# dGPS_mainBoard.net
KiCad netlist of a schematic drawn in EAGLE
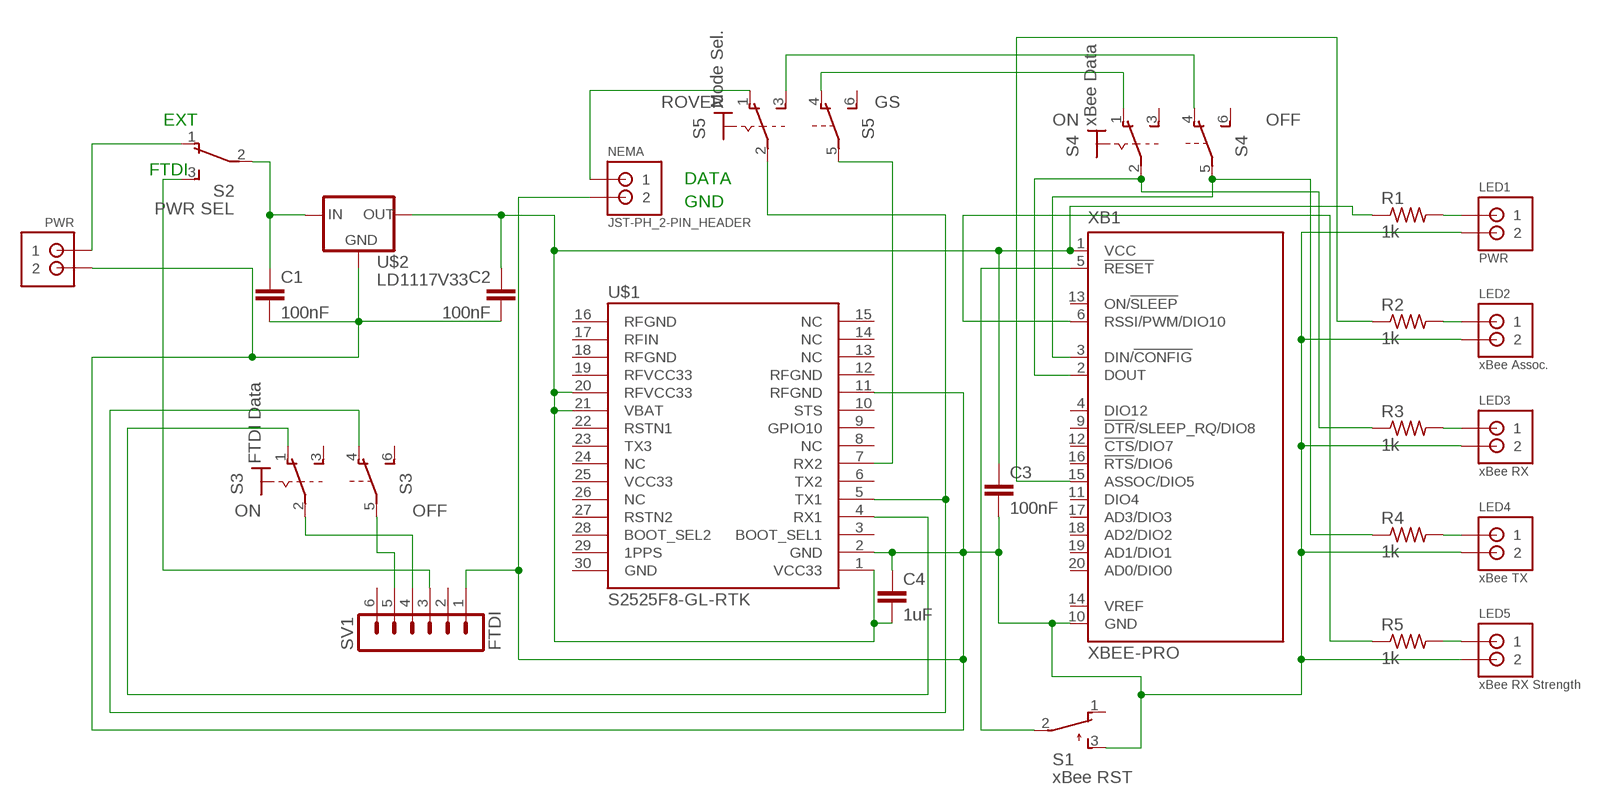
[diagram p0: schematic, sheet 1]

(export (version "E")
  (design (tool "Eeschema 10.0.6"))
  (components
    (comp (ref "C1")
      (value "100nF")
      (footprint "eagle-import:C2.5-5")
      (libsource (lib "eagle-import") (part "C2.5/5"))
    )
    (comp (ref "C2")
      (value "100nF")
      (footprint "eagle-import:C2.5-5")
      (libsource (lib "eagle-import") (part "C2.5/5"))
    )
    (comp (ref "C3")
      (value "100nF")
      (footprint "eagle-import:C2.5-5")
      (libsource (lib "eagle-import") (part "C2.5/5"))
    )
    (comp (ref "C4")
      (value "1uF")
      (footprint "eagle-import:C2.5-5")
      (libsource (lib "eagle-import") (part "C2.5/5"))
    )
    (comp (ref "LED1")
      (value "PWR")
      (footprint "eagle-import:JST_B2B-PH_HEADER")
      (libsource (lib "eagle-import") (part "JST-PH_2-PIN_HEADER"))
    )
    (comp (ref "LED2")
      (value "xBee Assoc.")
      (footprint "eagle-import:JST_B2B-PH_HEADER")
      (libsource (lib "eagle-import") (part "JST-PH_2-PIN_HEADER"))
    )
    (comp (ref "LED3")
      (value "xBee RX")
      (footprint "eagle-import:JST_B2B-PH_HEADER")
      (libsource (lib "eagle-import") (part "JST-PH_2-PIN_HEADER"))
    )
    (comp (ref "LED4")
      (value "xBee TX")
      (footprint "eagle-import:JST_B2B-PH_HEADER")
      (libsource (lib "eagle-import") (part "JST-PH_2-PIN_HEADER"))
    )
    (comp (ref "LED5")
      (value "xBee RX Strength")
      (footprint "eagle-import:JST_B2B-PH_HEADER")
      (libsource (lib "eagle-import") (part "JST-PH_2-PIN_HEADER"))
    )
    (comp (ref "NEMA")
      (value "JST-PH_2-PIN_HEADER")
      (footprint "eagle-import:JST_B2B-PH_HEADER")
      (libsource (lib "eagle-import") (part "JST-PH_2-PIN_HEADER"))
    )
    (comp (ref "PWR")
      (value "JST-PH_2-PIN_HEADER")
      (footprint "eagle-import:JST_B2B-PH_HEADER")
      (libsource (lib "eagle-import") (part "JST-PH_2-PIN_HEADER"))
    )
    (comp (ref "R1")
      (value "1k")
      (footprint "eagle-import:0204_5")
      (libsource (lib "eagle-import") (part "R-US_0204/5"))
    )
    (comp (ref "R2")
      (value "1k")
      (footprint "eagle-import:0204_5")
      (libsource (lib "eagle-import") (part "R-US_0204/5"))
    )
    (comp (ref "R3")
      (value "1k")
      (footprint "eagle-import:0204_5")
      (libsource (lib "eagle-import") (part "R-US_0204/5"))
    )
    (comp (ref "R4")
      (value "1k")
      (footprint "eagle-import:0204_5")
      (libsource (lib "eagle-import") (part "R-US_0204/5"))
    )
    (comp (ref "R5")
      (value "1k")
      (footprint "eagle-import:0204_5")
      (libsource (lib "eagle-import") (part "R-US_0204/5"))
    )
    (comp (ref "S1")
      (value "xBee RST")
      (footprint "eagle-import:TL3XYO")
      (libsource (lib "eagle-import") (part "TL32YO"))
    )
    (comp (ref "S2")
      (value "PWR SEL")
      (footprint "eagle-import:TL3XPO")
      (libsource (lib "eagle-import") (part "TL36PO"))
    )
    (comp (ref "S3")
      (value "FTDI Data")
      (footprint "eagle-import:320-938")
      (libsource (lib "eagle-import") (part "320-938"))
    )
    (comp (ref "S4")
      (value "xBee Data")
      (footprint "eagle-import:320-938")
      (libsource (lib "eagle-import") (part "320-938"))
    )
    (comp (ref "S5")
      (value "Mode Sel.")
      (footprint "eagle-import:320-938")
      (libsource (lib "eagle-import") (part "320-938"))
    )
    (comp (ref "SV1")
      (value "FTDI")
      (footprint "eagle-import:MA06-1")
      (libsource (lib "eagle-import") (part "MA06-1"))
    )
    (comp (ref "U$1")
      (value "S2525F8‐GL‐RTK")
      (footprint "eagle-import:NS-HP-GL2")
      (libsource (lib "eagle-import") (part "S2525F8‐GL‐RTK"))
    )
    (comp (ref "U$2")
      (value "LD1117V33")
      (footprint "eagle-import:LD1117V33")
      (libsource (lib "eagle-import") (part "LD1117V33"))
    )
    (comp (ref "XB1")
      (value "XBEE-PRO")
      (footprint "eagle-import:XBEE-PRO")
      (fields (field (name "MPN") "XBP24-AWI-001"))
      (libsource (lib "eagle-import") (part "XBEE-PRO"))
    )
  )
  (nets
    (net (code "1") (name "Net-(LED1-1)") (class "Default")
      (node (ref "LED1") (pin "P1") (pinfunction "1_P1") (pintype "bidirectional"))
      (node (ref "R1") (pin "2") (pinfunction "2_2") (pintype "passive"))
    )
    (net (code "2") (name "Net-(LED1-2)") (class "Default")
      (node (ref "C1") (pin "2") (pinfunction "2_2") (pintype "passive"))
      (node (ref "C2") (pin "2") (pinfunction "2_2") (pintype "passive"))
      (node (ref "C3") (pin "2") (pinfunction "2_2") (pintype "passive"))
      (node (ref "C4") (pin "1") (pinfunction "1_1") (pintype "passive"))
      (node (ref "LED1") (pin "P2") (pinfunction "2_P2") (pintype "bidirectional"))
      (node (ref "LED2") (pin "P2") (pinfunction "2_P2") (pintype "bidirectional"))
      (node (ref "LED3") (pin "P2") (pinfunction "2_P2") (pintype "bidirectional"))
      (node (ref "LED4") (pin "P2") (pinfunction "2_P2") (pintype "bidirectional"))
      (node (ref "LED5") (pin "P2") (pinfunction "2_P2") (pintype "bidirectional"))
      (node (ref "NEMA") (pin "P2") (pinfunction "2_P2") (pintype "bidirectional"))
      (node (ref "PWR") (pin "P2") (pinfunction "2_P2") (pintype "bidirectional"))
      (node (ref "S1") (pin "3") (pinfunction "S_3") (pintype "passive"))
      (node (ref "SV1") (pin "1") (pinfunction "1_1") (pintype "passive"))
      (node (ref "U$1") (pin "11") (pinfunction "RFGND_11") (pintype "bidirectional"))
      (node (ref "U$1") (pin "2") (pinfunction "GND_2") (pintype "bidirectional"))
      (node (ref "U$2") (pin "GND") (pinfunction "GND_GND") (pintype "input"))
      (node (ref "XB1") (pin "10") (pinfunction "GND_10") (pintype "power_in"))
    )
    (net (code "3") (name "Net-(LED2-1)") (class "Default")
      (node (ref "LED2") (pin "P1") (pinfunction "1_P1") (pintype "bidirectional"))
      (node (ref "R2") (pin "2") (pinfunction "2_2") (pintype "passive"))
    )
    (net (code "4") (name "Net-(LED3-1)") (class "Default")
      (node (ref "LED3") (pin "P1") (pinfunction "1_P1") (pintype "bidirectional"))
      (node (ref "R3") (pin "2") (pinfunction "2_2") (pintype "passive"))
    )
    (net (code "5") (name "Net-(LED4-1)") (class "Default")
      (node (ref "LED4") (pin "P1") (pinfunction "1_P1") (pintype "bidirectional"))
      (node (ref "R4") (pin "2") (pinfunction "2_2") (pintype "passive"))
    )
    (net (code "6") (name "Net-(LED5-1)") (class "Default")
      (node (ref "LED5") (pin "P1") (pinfunction "1_P1") (pintype "bidirectional"))
      (node (ref "R5") (pin "2") (pinfunction "2_2") (pintype "passive"))
    )
    (net (code "7") (name "Net-(NEMA-1)") (class "Default")
      (node (ref "NEMA") (pin "P1") (pinfunction "1_P1") (pintype "bidirectional"))
      (node (ref "S5") (pin "1") (pinfunction "O_1") (pintype "passive"))
    )
    (net (code "8") (name "Net-(PWR-1)") (class "Default")
      (node (ref "PWR") (pin "P1") (pinfunction "1_P1") (pintype "bidirectional"))
      (node (ref "S2") (pin "1") (pinfunction "O_1") (pintype "passive"))
    )
    (net (code "9") (name "Net-(S1-P)") (class "Default")
      (node (ref "S1") (pin "2") (pinfunction "P_2") (pintype "passive"))
      (node (ref "XB1") (pin "5") (pinfunction "~{RESET}_5") (pintype "input"))
    )
    (net (code "10") (name "Net-(S2-P)") (class "Default")
      (node (ref "C1") (pin "1") (pinfunction "1_1") (pintype "passive"))
      (node (ref "S2") (pin "2") (pinfunction "P_2") (pintype "passive"))
      (node (ref "U$2") (pin "IN") (pinfunction "IN_IN") (pintype "input"))
    )
    (net (code "11") (name "Net-(S2-S)") (class "Default")
      (node (ref "S2") (pin "3") (pinfunction "S_3") (pintype "passive"))
      (node (ref "SV1") (pin "3") (pinfunction "3_3") (pintype "passive"))
    )
    (net (code "12") (name "Net-(S3A-O)") (class "Default")
      (node (ref "S3") (pin "1") (pinfunction "O_1") (pintype "passive"))
      (node (ref "U$1") (pin "4") (pinfunction "RX1_4") (pintype "bidirectional"))
    )
    (net (code "13") (name "Net-(S3A-P)") (class "Default")
      (node (ref "S3") (pin "2") (pinfunction "P_2") (pintype "passive"))
      (node (ref "SV1") (pin "4") (pinfunction "4_4") (pintype "passive"))
    )
    (net (code "14") (name "Net-(S3B-O)") (class "Default")
      (node (ref "S3") (pin "4") (pinfunction "O_4") (pintype "passive"))
      (node (ref "S5") (pin "2") (pinfunction "P_2") (pintype "passive"))
      (node (ref "U$1") (pin "5") (pinfunction "TX1_5") (pintype "bidirectional"))
    )
    (net (code "15") (name "Net-(S3B-P)") (class "Default")
      (node (ref "S3") (pin "5") (pinfunction "P_5") (pintype "passive"))
      (node (ref "SV1") (pin "5") (pinfunction "5_5") (pintype "passive"))
    )
    (net (code "16") (name "Net-(S4A-O)") (class "Default")
      (node (ref "S4") (pin "1") (pinfunction "O_1") (pintype "passive"))
      (node (ref "S5") (pin "4") (pinfunction "O_4") (pintype "passive"))
    )
    (net (code "17") (name "Net-(S4A-P)") (class "Default")
      (node (ref "R3") (pin "1") (pinfunction "1_1") (pintype "passive"))
      (node (ref "S4") (pin "2") (pinfunction "P_2") (pintype "passive"))
      (node (ref "XB1") (pin "2") (pinfunction "DOUT_2") (pintype "output"))
    )
    (net (code "18") (name "Net-(S4B-O)") (class "Default")
      (node (ref "S4") (pin "4") (pinfunction "O_4") (pintype "passive"))
      (node (ref "S5") (pin "3") (pinfunction "S_3") (pintype "passive"))
    )
    (net (code "19") (name "Net-(S4B-P)") (class "Default")
      (node (ref "R4") (pin "1") (pinfunction "1_1") (pintype "passive"))
      (node (ref "S4") (pin "5") (pinfunction "P_5") (pintype "passive"))
      (node (ref "XB1") (pin "3") (pinfunction "DIN/~{CONFIG}_3") (pintype "input"))
    )
    (net (code "20") (name "Net-(S5B-P)") (class "Default")
      (node (ref "S5") (pin "5") (pinfunction "P_5") (pintype "passive"))
      (node (ref "U$1") (pin "7") (pinfunction "RX2_7") (pintype "bidirectional"))
    )
    (net (code "21") (name "Net-(U$1-VBAT)") (class "Default")
      (node (ref "C2") (pin "1") (pinfunction "1_1") (pintype "passive"))
      (node (ref "C3") (pin "1") (pinfunction "1_1") (pintype "passive"))
      (node (ref "C4") (pin "2") (pinfunction "2_2") (pintype "passive"))
      (node (ref "R1") (pin "1") (pinfunction "1_1") (pintype "passive"))
      (node (ref "U$1") (pin "1") (pinfunction "VCC33_1") (pintype "bidirectional"))
      (node (ref "U$1") (pin "20") (pinfunction "RFVCC33_20") (pintype "bidirectional"))
      (node (ref "U$1") (pin "21") (pinfunction "VBAT_21") (pintype "bidirectional"))
      (node (ref "U$2") (pin "OUT") (pinfunction "OUT_OUT") (pintype "output"))
      (node (ref "XB1") (pin "1") (pinfunction "VCC_1") (pintype "power_in"))
    )
    (net (code "22") (name "Net-(XB1-ASSOC{slash}DIO5)") (class "Default")
      (node (ref "R2") (pin "1") (pinfunction "1_1") (pintype "passive"))
      (node (ref "XB1") (pin "15") (pinfunction "ASSOC/DIO5_15") (pintype "bidirectional"))
    )
    (net (code "23") (name "Net-(XB1-RSSI{slash}PWM{slash}DIO10)") (class "Default")
      (node (ref "R5") (pin "1") (pinfunction "1_1") (pintype "passive"))
      (node (ref "XB1") (pin "6") (pinfunction "RSSI/PWM/DIO10_6") (pintype "output"))
    )
    (net (code "24") (name "unconnected-(S1-O-Pad1)") (class "Default")
      (node (ref "S1") (pin "1") (pinfunction "O_1") (pintype "passive"))
    )
    (net (code "25") (name "unconnected-(S3A-S-Pad3)") (class "Default")
      (node (ref "S3") (pin "3") (pinfunction "S_3") (pintype "passive"))
    )
    (net (code "26") (name "unconnected-(S3B-S-Pad6)") (class "Default")
      (node (ref "S3") (pin "6") (pinfunction "S_6") (pintype "passive"))
    )
    (net (code "27") (name "unconnected-(S4A-S-Pad3)") (class "Default")
      (node (ref "S4") (pin "3") (pinfunction "S_3") (pintype "passive"))
    )
    (net (code "28") (name "unconnected-(S4B-S-Pad6)") (class "Default")
      (node (ref "S4") (pin "6") (pinfunction "S_6") (pintype "passive"))
    )
    (net (code "29") (name "unconnected-(S5B-S-Pad6)") (class "Default")
      (node (ref "S5") (pin "6") (pinfunction "S_6") (pintype "passive"))
    )
    (net (code "30") (name "unconnected-(SV1-Pad2)") (class "Default")
      (node (ref "SV1") (pin "2") (pinfunction "2_2") (pintype "passive"))
    )
    (net (code "31") (name "unconnected-(SV1-Pad6)") (class "Default")
      (node (ref "SV1") (pin "6") (pinfunction "6_6") (pintype "passive"))
    )
    (net (code "32") (name "unconnected-(U$1-1PPS-Pad29)") (class "Default")
      (node (ref "U$1") (pin "29") (pinfunction "1PPS_29") (pintype "bidirectional"))
    )
    (net (code "33") (name "unconnected-(U$1-BOOT_SEL1-Pad3)") (class "Default")
      (node (ref "U$1") (pin "3") (pinfunction "BOOT_SEL1_3") (pintype "bidirectional"))
    )
    (net (code "34") (name "unconnected-(U$1-BOOT_SEL2-Pad28)") (class "Default")
      (node (ref "U$1") (pin "28") (pinfunction "BOOT_SEL2_28") (pintype "bidirectional"))
    )
    (net (code "35") (name "unconnected-(U$1-GND-Pad30)") (class "Default")
      (node (ref "U$1") (pin "30") (pinfunction "GND_30") (pintype "bidirectional"))
    )
    (net (code "36") (name "unconnected-(U$1-GPIO10-Pad9)") (class "Default")
      (node (ref "U$1") (pin "9") (pinfunction "GPIO10_9") (pintype "bidirectional"))
    )
    (net (code "37") (name "unconnected-(U$1-NC-Pad8)") (class "Default")
      (node (ref "U$1") (pin "8") (pinfunction "NC_8") (pintype "bidirectional"))
    )
    (net (code "38") (name "unconnected-(U$1-NC-Pad13)") (class "Default")
      (node (ref "U$1") (pin "13") (pinfunction "NC_13") (pintype "bidirectional"))
    )
    (net (code "39") (name "unconnected-(U$1-NC-Pad14)") (class "Default")
      (node (ref "U$1") (pin "14") (pinfunction "NC_14") (pintype "bidirectional"))
    )
    (net (code "40") (name "unconnected-(U$1-NC-Pad15)") (class "Default")
      (node (ref "U$1") (pin "15") (pinfunction "NC_15") (pintype "bidirectional"))
    )
    (net (code "41") (name "unconnected-(U$1-NC-Pad24)") (class "Default")
      (node (ref "U$1") (pin "24") (pinfunction "NC_24") (pintype "bidirectional"))
    )
    (net (code "42") (name "unconnected-(U$1-NC-Pad26)") (class "Default")
      (node (ref "U$1") (pin "26") (pinfunction "NC_26") (pintype "bidirectional"))
    )
    (net (code "43") (name "unconnected-(U$1-RFGND-Pad12)") (class "Default")
      (node (ref "U$1") (pin "12") (pinfunction "RFGND_12") (pintype "bidirectional"))
    )
    (net (code "44") (name "unconnected-(U$1-RFGND-Pad16)") (class "Default")
      (node (ref "U$1") (pin "16") (pinfunction "RFGND_16") (pintype "bidirectional"))
    )
    (net (code "45") (name "unconnected-(U$1-RFGND-Pad18)") (class "Default")
      (node (ref "U$1") (pin "18") (pinfunction "RFGND_18") (pintype "bidirectional"))
    )
    (net (code "46") (name "unconnected-(U$1-RFIN-Pad17)") (class "Default")
      (node (ref "U$1") (pin "17") (pinfunction "RFIN_17") (pintype "bidirectional"))
    )
    (net (code "47") (name "unconnected-(U$1-RFVCC33-Pad19)") (class "Default")
      (node (ref "U$1") (pin "19") (pinfunction "RFVCC33_19") (pintype "bidirectional"))
    )
    (net (code "48") (name "unconnected-(U$1-RSTN1-Pad22)") (class "Default")
      (node (ref "U$1") (pin "22") (pinfunction "RSTN1_22") (pintype "bidirectional"))
    )
    (net (code "49") (name "unconnected-(U$1-RSTN2-Pad27)") (class "Default")
      (node (ref "U$1") (pin "27") (pinfunction "RSTN2_27") (pintype "bidirectional"))
    )
    (net (code "50") (name "unconnected-(U$1-STS-Pad10)") (class "Default")
      (node (ref "U$1") (pin "10") (pinfunction "STS_10") (pintype "bidirectional"))
    )
    (net (code "51") (name "unconnected-(U$1-TX2-Pad6)") (class "Default")
      (node (ref "U$1") (pin "6") (pinfunction "TX2_6") (pintype "bidirectional"))
    )
    (net (code "52") (name "unconnected-(U$1-TX3-Pad23)") (class "Default")
      (node (ref "U$1") (pin "23") (pinfunction "TX3_23") (pintype "bidirectional"))
    )
    (net (code "53") (name "unconnected-(U$1-VCC33-Pad25)") (class "Default")
      (node (ref "U$1") (pin "25") (pinfunction "VCC33_25") (pintype "bidirectional"))
    )
    (net (code "54") (name "unconnected-(XB1-AD0{slash}DIO0-Pad20)") (class "Default")
      (node (ref "XB1") (pin "20") (pinfunction "AD0/DIO0_20") (pintype "bidirectional"))
    )
    (net (code "55") (name "unconnected-(XB1-AD1{slash}DIO1-Pad19)") (class "Default")
      (node (ref "XB1") (pin "19") (pinfunction "AD1/DIO1_19") (pintype "bidirectional"))
    )
    (net (code "56") (name "unconnected-(XB1-AD2{slash}DIO2-Pad18)") (class "Default")
      (node (ref "XB1") (pin "18") (pinfunction "AD2/DIO2_18") (pintype "bidirectional"))
    )
    (net (code "57") (name "unconnected-(XB1-AD3{slash}DIO3-Pad17)") (class "Default")
      (node (ref "XB1") (pin "17") (pinfunction "AD3/DIO3_17") (pintype "bidirectional"))
    )
    (net (code "58") (name "unconnected-(XB1-DIO4-Pad11)") (class "Default")
      (node (ref "XB1") (pin "11") (pinfunction "DIO4_11") (pintype "bidirectional"))
    )
    (net (code "59") (name "unconnected-(XB1-DIO12-Pad4)") (class "Default")
      (node (ref "XB1") (pin "4") (pinfunction "DIO12_4") (pintype "bidirectional"))
    )
    (net (code "60") (name "unconnected-(XB1-ON{slash}~{SLEEP}-Pad13)") (class "Default")
      (node (ref "XB1") (pin "13") (pinfunction "ON/~{SLEEP}_13") (pintype "output"))
    )
    (net (code "61") (name "unconnected-(XB1-VREF-Pad14)") (class "Default")
      (node (ref "XB1") (pin "14") (pinfunction "VREF_14") (pintype "input"))
    )
    (net (code "62") (name "unconnected-(XB1-~{CTS}{slash}DIO7-Pad12)") (class "Default")
      (node (ref "XB1") (pin "12") (pinfunction "~{CTS}/DIO7_12") (pintype "bidirectional"))
    )
    (net (code "63") (name "unconnected-(XB1-~{DTR}{slash}SLEEP_RQ{slash}DIO8-Pad9)") (class "Default")
      (node (ref "XB1") (pin "9") (pinfunction "~{DTR}/SLEEP_RQ/DIO8_9") (pintype "bidirectional"))
    )
    (net (code "64") (name "unconnected-(XB1-~{RTS}{slash}DIO6-Pad16)") (class "Default")
      (node (ref "XB1") (pin "16") (pinfunction "~{RTS}/DIO6_16") (pintype "bidirectional"))
    )
  )
)
